# XL1507.net
KiCad netlist of a schematic drawn in Altium Designer
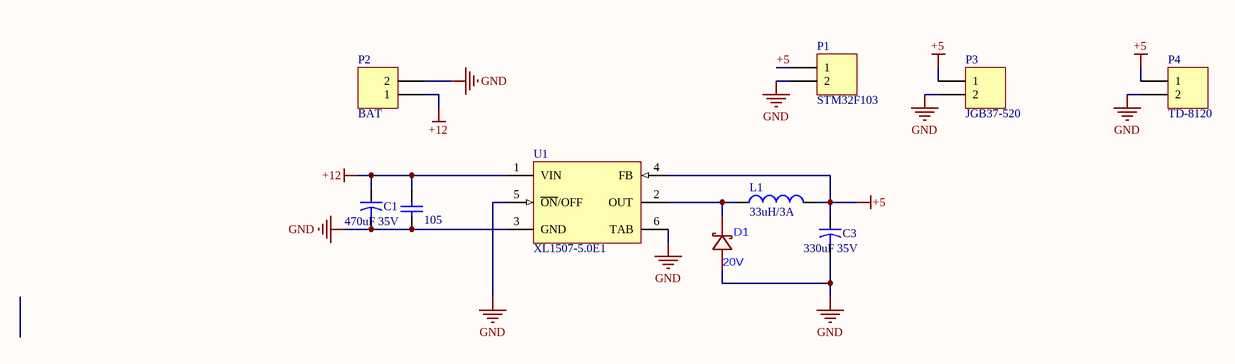
[diagram p0: XL1507.SchDoc]

(export (version "E")
  (design (tool "Eeschema 10.0.6"))
  (components
    (comp (ref "C1")
      (value "470uF 35V")
      (footprint "C6.3X6.3")
      (description "EMZS350ARA471MHA0G")
      (fields (field (name "PUBLISHER") "Altium Limited"))
      (libsource (lib "XL1507_5.0E") (part "CAP2"))
    )
    (comp (ref "C2")
      (value "105")
      (footprint "C1210_M")
      (description "CL32B105KBHNNNE")
      (libsource (lib "XL1507_5.0E") (part "C"))
    )
    (comp (ref "C3")
      (value "330uF 35V")
      (footprint "C6.3X6.3")
      (description "UCM1V331MNL1GS")
      (fields (field (name "PUBLISHER") "Altium Limited"))
      (libsource (lib "XL1507_5.0E") (part "CAP2"))
    )
    (comp (ref "D1")
      (value "20V")
      (footprint "DO-214")
      (description "SS12-E3/61T")
      (libsource (lib "altium-import") (part "root_1_1N5820RLG_"))
    )
    (comp (ref "L1")
      (value "33uH/3A")
      (footprint "L7X7")
      (description "FAUL0650-330MT")
      (fields (field (name "PUBLISHER") "Altium Limited"))
      (libsource (lib "XL1507_5.0E") (part "Inductor"))
    )
    (comp (ref "P1")
      (value "STM32F103")
      (footprint "XT30-M")
      (description "Header, 2-Pin")
      (fields (field (name "PUBLISHER") "Altium Limited"))
      (libsource (lib "") (part "Header 2_1"))
    )
    (comp (ref "P2")
      (value "BAT")
      (footprint "XT30-M")
      (description "Header, 2-Pin")
      (fields (field (name "PUBLISHER") "Altium Limited"))
      (libsource (lib "Miscellaneous Connectors") (part "Header 2"))
    )
    (comp (ref "P3")
      (value "JGB37-520")
      (footprint "XT30-M")
      (description "Header, 2-Pin")
      (fields (field (name "PUBLISHER") "Altium Limited"))
      (libsource (lib "") (part "Header 2_1"))
    )
    (comp (ref "P4")
      (value "TD-8120")
      (footprint "XT30-M")
      (description "Header, 2-Pin")
      (fields (field (name "PUBLISHER") "Altium Limited"))
      (libsource (lib "") (part "Header 2_1"))
    )
    (comp (ref "U1")
      (value "XL1507-5.0E1")
      (footprint "TO252-5")
      (description "12V-5V")
      (fields
        (field (name "PARTNUMBER") "LM2596S-5.0")
        (field (name "MANUFACTURER") "National Semiconductor")
      )
      (libsource (lib "XL1507_5.0E") (part "LM2596S-5.0"))
    )
  )
  (nets
    (net (code "1") (name "+5") (class "Default")
      (node (ref "C3") (pin "1") (pinfunction "1_1") (pintype "passive"))
      (node (ref "L1") (pin "2") (pinfunction "2_2") (pintype "passive"))
      (node (ref "P1") (pin "1") (pinfunction "1_1") (pintype "passive"))
      (node (ref "P3") (pin "1") (pinfunction "1_1") (pintype "passive"))
      (node (ref "P4") (pin "1") (pinfunction "1_1") (pintype "passive"))
      (node (ref "U1") (pin "4") (pinfunction "FB_4") (pintype "input"))
    )
    (net (code "2") (name "+12") (class "Default")
      (node (ref "C1") (pin "1") (pinfunction "1_1") (pintype "passive"))
      (node (ref "C2") (pin "2") (pinfunction "2_2") (pintype "passive"))
      (node (ref "P2") (pin "1") (pinfunction "1_1") (pintype "passive"))
      (node (ref "U1") (pin "1") (pinfunction "VIN_1") (pintype "power_in"))
    )
    (net (code "3") (name "GND") (class "Default")
      (node (ref "C1") (pin "2") (pinfunction "2_2") (pintype "passive"))
      (node (ref "C2") (pin "1") (pinfunction "1_1") (pintype "passive"))
      (node (ref "C3") (pin "2") (pinfunction "2_2") (pintype "passive"))
      (node (ref "D1") (pin "1") (pinfunction "A_1") (pintype "passive"))
      (node (ref "P1") (pin "2") (pinfunction "2_2") (pintype "passive"))
      (node (ref "P2") (pin "2") (pinfunction "2_2") (pintype "passive"))
      (node (ref "P3") (pin "2") (pinfunction "2_2") (pintype "passive"))
      (node (ref "P4") (pin "2") (pinfunction "2_2") (pintype "passive"))
      (node (ref "U1") (pin "3") (pinfunction "GND_3") (pintype "power_in"))
      (node (ref "U1") (pin "5") (pinfunction "~{ON}/OFF_5") (pintype "input"))
      (node (ref "U1") (pin "6") (pinfunction "TAB_6") (pintype "power_in"))
    )
    (net (code "4") (name "Net-(D1-K)") (class "Default")
      (node (ref "D1") (pin "2") (pinfunction "K_2") (pintype "passive"))
      (node (ref "L1") (pin "1") (pinfunction "1_1") (pintype "passive"))
      (node (ref "U1") (pin "2") (pinfunction "OUT_2") (pintype "power_in"))
    )
  )
)
